# ICEBoard_working.net
KiCad netlist of a schematic drawn in Altium Designer
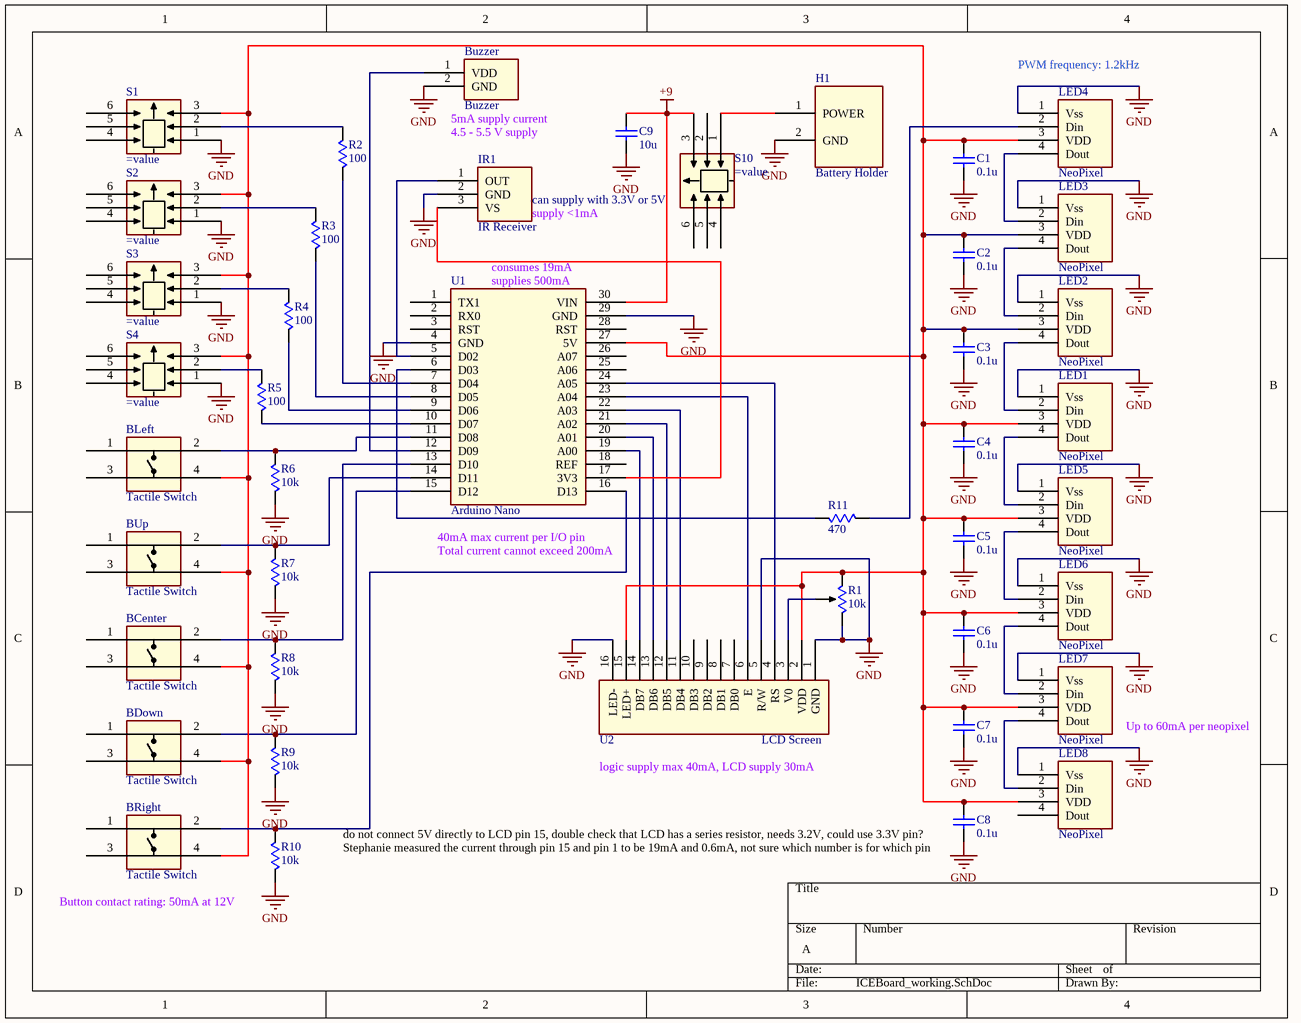
[diagram p0: ICEBoard_working.SchDoc]

(export (version "E")
  (design (tool "Eeschema 10.0.6"))
  (components
    (comp (ref "BCenter")
      (value "Tactile Switch")
      (footprint "PTS645")
      (libsource (lib "PTS645") (part "PTS645"))
    )
    (comp (ref "BDown")
      (value "Tactile Switch")
      (footprint "PTS645")
      (libsource (lib "PTS645") (part "PTS645"))
    )
    (comp (ref "BLeft")
      (value "Tactile Switch")
      (footprint "PTS645")
      (libsource (lib "PTS645") (part "PTS645"))
    )
    (comp (ref "BRight")
      (value "Tactile Switch")
      (footprint "PTS645")
      (libsource (lib "PTS645") (part "PTS645"))
    )
    (comp (ref "BUp")
      (value "Tactile Switch")
      (footprint "PTS645")
      (libsource (lib "PTS645") (part "PTS645"))
    )
    (comp (ref "Buzzer")
      (value "Buzzer")
      (footprint "TP124005")
      (libsource (lib "TP124005") (part "TP124005"))
    )
    (comp (ref "C1") (value "0.1u") (footprint "Capacitor") (libsource (lib "Capacitor") (part "Capacitor")))
    (comp (ref "C2") (value "0.1u") (footprint "Capacitor") (libsource (lib "Capacitor") (part "Capacitor")))
    (comp (ref "C3") (value "0.1u") (footprint "Capacitor") (libsource (lib "Capacitor") (part "Capacitor")))
    (comp (ref "C4") (value "0.1u") (footprint "Capacitor") (libsource (lib "Capacitor") (part "Capacitor")))
    (comp (ref "C5") (value "0.1u") (footprint "Capacitor") (libsource (lib "Capacitor") (part "Capacitor")))
    (comp (ref "C6") (value "0.1u") (footprint "Capacitor") (libsource (lib "Capacitor") (part "Capacitor")))
    (comp (ref "C7") (value "0.1u") (footprint "Capacitor") (libsource (lib "Capacitor") (part "Capacitor")))
    (comp (ref "C8") (value "0.1u") (footprint "Capacitor") (libsource (lib "Capacitor") (part "Capacitor")))
    (comp (ref "C9")
      (value "10u")
      (footprint "PCBComponent_1")
      (libsource (lib "Capacitor") (part "Capacitor"))
    )
    (comp (ref "H1") (value "Battery Holder") (footprint "BH9VPC") (libsource (lib "BH9VPC") (part "BH9VPC")))
    (comp (ref "IR1")
      (value "IR Receiver")
      (footprint "TSOP382")
      (libsource (lib "TSOP382") (part "TSOP382"))
    )
    (comp (ref "LED1")
      (value "NeoPixel")
      (footprint "NeoPixel")
      (libsource (lib "NeoPixel") (part "NeoPixel"))
    )
    (comp (ref "LED2")
      (value "NeoPixel")
      (footprint "NeoPixel")
      (libsource (lib "NeoPixel") (part "NeoPixel"))
    )
    (comp (ref "LED3")
      (value "NeoPixel")
      (footprint "NeoPixel")
      (libsource (lib "NeoPixel") (part "NeoPixel"))
    )
    (comp (ref "LED4")
      (value "NeoPixel")
      (footprint "NeoPixel")
      (libsource (lib "NeoPixel") (part "NeoPixel"))
    )
    (comp (ref "LED5")
      (value "NeoPixel")
      (footprint "NeoPixel")
      (libsource (lib "NeoPixel") (part "NeoPixel"))
    )
    (comp (ref "LED6")
      (value "NeoPixel")
      (footprint "NeoPixel")
      (libsource (lib "NeoPixel") (part "NeoPixel"))
    )
    (comp (ref "LED7")
      (value "NeoPixel")
      (footprint "NeoPixel")
      (libsource (lib "NeoPixel") (part "NeoPixel"))
    )
    (comp (ref "LED8")
      (value "NeoPixel")
      (footprint "NeoPixel")
      (libsource (lib "NeoPixel") (part "NeoPixel"))
    )
    (comp (ref "R1")
      (value "10k")
      (footprint "TC33X")
      (libsource (lib "Resistor - Variable") (part "Resistor - Variable"))
    )
    (comp (ref "R2") (value "100") (footprint "Resistor1608") (libsource (lib "Resistor") (part "Resistor")))
    (comp (ref "R3") (value "100") (footprint "Resistor1608") (libsource (lib "Resistor") (part "Resistor")))
    (comp (ref "R4") (value "100") (footprint "Resistor1608") (libsource (lib "Resistor") (part "Resistor")))
    (comp (ref "R5") (value "100") (footprint "Resistor1608") (libsource (lib "Resistor") (part "Resistor")))
    (comp (ref "R6") (value "10k") (footprint "Resistor1608") (libsource (lib "Resistor") (part "Resistor")))
    (comp (ref "R7") (value "10k") (footprint "Resistor1608") (libsource (lib "Resistor") (part "Resistor")))
    (comp (ref "R8") (value "10k") (footprint "Resistor1608") (libsource (lib "Resistor") (part "Resistor")))
    (comp (ref "R9") (value "10k") (footprint "Resistor1608") (libsource (lib "Resistor") (part "Resistor")))
    (comp (ref "R10") (value "10k") (footprint "Resistor1608") (libsource (lib "Resistor") (part "Resistor")))
    (comp (ref "R11") (value "470") (footprint "Resistor1608") (libsource (lib "Resistor") (part "Resistor")))
    (comp (ref "S1") (value "~") (footprint "MHSS1104") (libsource (lib "MHSS1104") (part "MHSS1104")))
    (comp (ref "S2") (value "~") (footprint "MHSS1104") (libsource (lib "MHSS1104") (part "MHSS1104")))
    (comp (ref "S3") (value "~") (footprint "MHSS1104") (libsource (lib "MHSS1104") (part "MHSS1104")))
    (comp (ref "S4") (value "~") (footprint "MHSS1104") (libsource (lib "MHSS1104") (part "MHSS1104")))
    (comp (ref "S10") (value "~") (footprint "MHSS1104") (libsource (lib "") (part "MHSS1104_1")))
    (comp (ref "U1")
      (value "Arduino Nano")
      (footprint "ArduinoNano")
      (libsource (lib "ArduinoNano") (part "ArduinoNano"))
    )
    (comp (ref "U2")
      (value "LCD Screen")
      (footprint "TC1602A-01T")
      (libsource (lib "TC1602A-01T") (part "TC1602A-01T"))
    )
  )
  (nets
    (net (code "1") (name "+9") (class "Default")
      (node (ref "C9") (pin "1") (pinfunction "1_1") (pintype "passive"))
      (node (ref "S10") (pin "3") (pintype "passive"))
      (node (ref "U1") (pin "30") (pinfunction "VIN_30") (pintype "passive"))
    )
    (net (code "2") (name "GND") (class "Default")
      (node (ref "Buzzer") (pin "2") (pinfunction "GND_2") (pintype "passive"))
      (node (ref "C1") (pin "2") (pinfunction "2_2") (pintype "passive"))
      (node (ref "C2") (pin "2") (pinfunction "2_2") (pintype "passive"))
      (node (ref "C3") (pin "2") (pinfunction "2_2") (pintype "passive"))
      (node (ref "C4") (pin "2") (pinfunction "2_2") (pintype "passive"))
      (node (ref "C5") (pin "2") (pinfunction "2_2") (pintype "passive"))
      (node (ref "C6") (pin "2") (pinfunction "2_2") (pintype "passive"))
      (node (ref "C7") (pin "2") (pinfunction "2_2") (pintype "passive"))
      (node (ref "C8") (pin "2") (pinfunction "2_2") (pintype "passive"))
      (node (ref "C9") (pin "2") (pinfunction "2_2") (pintype "passive"))
      (node (ref "H1") (pin "2") (pinfunction "GND_2") (pintype "passive"))
      (node (ref "IR1") (pin "2") (pinfunction "GND_2") (pintype "passive"))
      (node (ref "LED1") (pin "1") (pinfunction "Vss_1") (pintype "passive"))
      (node (ref "LED2") (pin "1") (pinfunction "Vss_1") (pintype "passive"))
      (node (ref "LED3") (pin "1") (pinfunction "Vss_1") (pintype "passive"))
      (node (ref "LED4") (pin "1") (pinfunction "Vss_1") (pintype "passive"))
      (node (ref "LED5") (pin "1") (pinfunction "Vss_1") (pintype "passive"))
      (node (ref "LED6") (pin "1") (pinfunction "Vss_1") (pintype "passive"))
      (node (ref "LED7") (pin "1") (pinfunction "Vss_1") (pintype "passive"))
      (node (ref "LED8") (pin "1") (pinfunction "Vss_1") (pintype "passive"))
      (node (ref "R1") (pin "1") (pinfunction "1_1") (pintype "passive"))
      (node (ref "R10") (pin "1") (pinfunction "1_1") (pintype "passive"))
      (node (ref "R6") (pin "1") (pinfunction "1_1") (pintype "passive"))
      (node (ref "R7") (pin "1") (pinfunction "1_1") (pintype "passive"))
      (node (ref "R8") (pin "1") (pinfunction "1_1") (pintype "passive"))
      (node (ref "R9") (pin "1") (pinfunction "1_1") (pintype "passive"))
      (node (ref "S1") (pin "1") (pintype "passive"))
      (node (ref "S2") (pin "1") (pintype "passive"))
      (node (ref "S3") (pin "1") (pintype "passive"))
      (node (ref "S4") (pin "1") (pintype "passive"))
      (node (ref "U1") (pin "29") (pinfunction "GND_29") (pintype "passive"))
      (node (ref "U1") (pin "4") (pinfunction "GND_4") (pintype "passive"))
      (node (ref "U2") (pin "1") (pinfunction "GND_1") (pintype "passive"))
      (node (ref "U2") (pin "16") (pinfunction "LED-_16") (pintype "passive"))
      (node (ref "U2") (pin "5") (pinfunction "R/W_5") (pintype "passive"))
    )
    (net (code "3") (name "Net-(Buzzer-VDD)") (class "Default")
      (node (ref "Buzzer") (pin "1") (pinfunction "VDD_1") (pintype "passive"))
      (node (ref "U1") (pin "12") (pinfunction "D09_12") (pintype "passive"))
    )
    (net (code "4") (name "Net-(H1-POWER)") (class "Default")
      (node (ref "H1") (pin "1") (pinfunction "POWER_1") (pintype "passive"))
      (node (ref "S10") (pin "1") (pintype "passive"))
    )
    (net (code "5") (name "Net-(IR1-OUT)") (class "Default")
      (node (ref "IR1") (pin "1") (pinfunction "OUT_1") (pintype "passive"))
      (node (ref "U1") (pin "5") (pinfunction "D02_5") (pintype "passive"))
    )
    (net (code "6") (name "Net-(IR1-VS)") (class "Default")
      (node (ref "IR1") (pin "3") (pinfunction "VS_3") (pintype "passive"))
      (node (ref "U1") (pin "17") (pinfunction "3V3_17") (pintype "passive"))
    )
    (net (code "7") (name "Net-(LED1-Din)") (class "Default")
      (node (ref "LED1") (pin "2") (pinfunction "Din_2") (pintype "passive"))
      (node (ref "LED2") (pin "4") (pinfunction "Dout_4") (pintype "passive"))
    )
    (net (code "8") (name "Net-(LED1-Dout)") (class "Default")
      (node (ref "LED1") (pin "4") (pinfunction "Dout_4") (pintype "passive"))
      (node (ref "LED5") (pin "2") (pinfunction "Din_2") (pintype "passive"))
    )
    (net (code "9") (name "Net-(LED1-VDD)") (class "Default")
      (node (ref "BCenter") (pin "4") (pintype "passive"))
      (node (ref "BDown") (pin "4") (pintype "passive"))
      (node (ref "BLeft") (pin "4") (pintype "passive"))
      (node (ref "BRight") (pin "4") (pintype "passive"))
      (node (ref "BUp") (pin "4") (pintype "passive"))
      (node (ref "C1") (pin "1") (pinfunction "1_1") (pintype "passive"))
      (node (ref "C2") (pin "1") (pinfunction "1_1") (pintype "passive"))
      (node (ref "C3") (pin "1") (pinfunction "1_1") (pintype "passive"))
      (node (ref "C4") (pin "1") (pinfunction "1_1") (pintype "passive"))
      (node (ref "C5") (pin "1") (pinfunction "1_1") (pintype "passive"))
      (node (ref "C6") (pin "1") (pinfunction "1_1") (pintype "passive"))
      (node (ref "C7") (pin "1") (pinfunction "1_1") (pintype "passive"))
      (node (ref "C8") (pin "1") (pinfunction "1_1") (pintype "passive"))
      (node (ref "LED1") (pin "3") (pinfunction "VDD_3") (pintype "passive"))
      (node (ref "LED2") (pin "3") (pinfunction "VDD_3") (pintype "passive"))
      (node (ref "LED3") (pin "3") (pinfunction "VDD_3") (pintype "passive"))
      (node (ref "LED4") (pin "3") (pinfunction "VDD_3") (pintype "passive"))
      (node (ref "LED5") (pin "3") (pinfunction "VDD_3") (pintype "passive"))
      (node (ref "LED6") (pin "3") (pinfunction "VDD_3") (pintype "passive"))
      (node (ref "LED7") (pin "3") (pinfunction "VDD_3") (pintype "passive"))
      (node (ref "LED8") (pin "3") (pinfunction "VDD_3") (pintype "passive"))
      (node (ref "R1") (pin "3") (pinfunction "3_3") (pintype "passive"))
      (node (ref "S1") (pin "3") (pintype "passive"))
      (node (ref "S2") (pin "3") (pintype "passive"))
      (node (ref "S3") (pin "3") (pintype "passive"))
      (node (ref "S4") (pin "3") (pintype "passive"))
      (node (ref "U1") (pin "27") (pinfunction "5V_27") (pintype "passive"))
      (node (ref "U2") (pin "15") (pinfunction "LED+_15") (pintype "passive"))
      (node (ref "U2") (pin "2") (pinfunction "VDD_2") (pintype "passive"))
    )
    (net (code "10") (name "Net-(LED2-Din)") (class "Default")
      (node (ref "LED2") (pin "2") (pinfunction "Din_2") (pintype "passive"))
      (node (ref "LED3") (pin "4") (pinfunction "Dout_4") (pintype "passive"))
    )
    (net (code "11") (name "Net-(LED3-Din)") (class "Default")
      (node (ref "LED3") (pin "2") (pinfunction "Din_2") (pintype "passive"))
      (node (ref "LED4") (pin "4") (pinfunction "Dout_4") (pintype "passive"))
    )
    (net (code "12") (name "Net-(LED4-Din)") (class "Default")
      (node (ref "LED4") (pin "2") (pinfunction "Din_2") (pintype "passive"))
      (node (ref "R11") (pin "2") (pinfunction "2_2") (pintype "passive"))
    )
    (net (code "13") (name "Net-(LED5-Dout)") (class "Default")
      (node (ref "LED5") (pin "4") (pinfunction "Dout_4") (pintype "passive"))
      (node (ref "LED6") (pin "2") (pinfunction "Din_2") (pintype "passive"))
    )
    (net (code "14") (name "Net-(LED6-Dout)") (class "Default")
      (node (ref "LED6") (pin "4") (pinfunction "Dout_4") (pintype "passive"))
      (node (ref "LED7") (pin "2") (pinfunction "Din_2") (pintype "passive"))
    )
    (net (code "15") (name "Net-(LED7-Dout)") (class "Default")
      (node (ref "LED7") (pin "4") (pinfunction "Dout_4") (pintype "passive"))
      (node (ref "LED8") (pin "2") (pinfunction "Din_2") (pintype "passive"))
    )
    (net (code "16") (name "Net-(R2-Pad2)") (class "Default")
      (node (ref "R2") (pin "2") (pinfunction "2_2") (pintype "passive"))
      (node (ref "S1") (pin "2") (pintype "passive"))
    )
    (net (code "17") (name "Net-(R3-Pad2)") (class "Default")
      (node (ref "R3") (pin "2") (pinfunction "2_2") (pintype "passive"))
      (node (ref "S2") (pin "2") (pintype "passive"))
    )
    (net (code "18") (name "Net-(R4-Pad2)") (class "Default")
      (node (ref "R4") (pin "2") (pinfunction "2_2") (pintype "passive"))
      (node (ref "S3") (pin "2") (pintype "passive"))
    )
    (net (code "19") (name "Net-(R5-Pad2)") (class "Default")
      (node (ref "R5") (pin "2") (pinfunction "2_2") (pintype "passive"))
      (node (ref "S4") (pin "2") (pintype "passive"))
    )
    (net (code "20") (name "Net-(U1-A00)") (class "Default")
      (node (ref "U1") (pin "19") (pinfunction "A00_19") (pintype "passive"))
      (node (ref "U2") (pin "14") (pinfunction "DB7_14") (pintype "passive"))
    )
    (net (code "21") (name "Net-(U1-A01)") (class "Default")
      (node (ref "U1") (pin "20") (pinfunction "A01_20") (pintype "passive"))
      (node (ref "U2") (pin "13") (pinfunction "DB6_13") (pintype "passive"))
    )
    (net (code "22") (name "Net-(U1-A02)") (class "Default")
      (node (ref "U1") (pin "21") (pinfunction "A02_21") (pintype "passive"))
      (node (ref "U2") (pin "12") (pinfunction "DB5_12") (pintype "passive"))
    )
    (net (code "23") (name "Net-(U1-A03)") (class "Default")
      (node (ref "U1") (pin "22") (pinfunction "A03_22") (pintype "passive"))
      (node (ref "U2") (pin "11") (pinfunction "DB4_11") (pintype "passive"))
    )
    (net (code "24") (name "Net-(U1-A04)") (class "Default")
      (node (ref "U1") (pin "23") (pinfunction "A04_23") (pintype "passive"))
      (node (ref "U2") (pin "6") (pinfunction "E_6") (pintype "passive"))
    )
    (net (code "25") (name "Net-(U1-A05)") (class "Default")
      (node (ref "U1") (pin "24") (pinfunction "A05_24") (pintype "passive"))
      (node (ref "U2") (pin "4") (pinfunction "RS_4") (pintype "passive"))
    )
    (net (code "26") (name "Net-(U1-D03)") (class "Default")
      (node (ref "R11") (pin "1") (pinfunction "1_1") (pintype "passive"))
      (node (ref "U1") (pin "6") (pinfunction "D03_6") (pintype "passive"))
    )
    (net (code "27") (name "Net-(U1-D04)") (class "Default")
      (node (ref "R2") (pin "1") (pinfunction "1_1") (pintype "passive"))
      (node (ref "U1") (pin "7") (pinfunction "D04_7") (pintype "passive"))
    )
    (net (code "28") (name "Net-(U1-D05)") (class "Default")
      (node (ref "R3") (pin "1") (pinfunction "1_1") (pintype "passive"))
      (node (ref "U1") (pin "8") (pinfunction "D05_8") (pintype "passive"))
    )
    (net (code "29") (name "Net-(U1-D06)") (class "Default")
      (node (ref "R4") (pin "1") (pinfunction "1_1") (pintype "passive"))
      (node (ref "U1") (pin "9") (pinfunction "D06_9") (pintype "passive"))
    )
    (net (code "30") (name "Net-(U1-D07)") (class "Default")
      (node (ref "R5") (pin "1") (pinfunction "1_1") (pintype "passive"))
      (node (ref "U1") (pin "10") (pinfunction "D07_10") (pintype "passive"))
    )
    (net (code "31") (name "Net-(U1-D08)") (class "Default")
      (node (ref "BLeft") (pin "2") (pintype "passive"))
      (node (ref "R6") (pin "2") (pinfunction "2_2") (pintype "passive"))
      (node (ref "U1") (pin "11") (pinfunction "D08_11") (pintype "passive"))
    )
    (net (code "32") (name "Net-(U1-D10)") (class "Default")
      (node (ref "BCenter") (pin "2") (pintype "passive"))
      (node (ref "R8") (pin "2") (pinfunction "2_2") (pintype "passive"))
      (node (ref "U1") (pin "13") (pinfunction "D10_13") (pintype "passive"))
    )
    (net (code "33") (name "Net-(U1-D11)") (class "Default")
      (node (ref "BUp") (pin "2") (pintype "passive"))
      (node (ref "R7") (pin "2") (pinfunction "2_2") (pintype "passive"))
      (node (ref "U1") (pin "14") (pinfunction "D11_14") (pintype "passive"))
    )
    (net (code "34") (name "Net-(U1-D12)") (class "Default")
      (node (ref "BDown") (pin "2") (pintype "passive"))
      (node (ref "R9") (pin "2") (pinfunction "2_2") (pintype "passive"))
      (node (ref "U1") (pin "15") (pinfunction "D12_15") (pintype "passive"))
    )
    (net (code "35") (name "Net-(U1-D13)") (class "Default")
      (node (ref "BRight") (pin "2") (pintype "passive"))
      (node (ref "R10") (pin "2") (pinfunction "2_2") (pintype "passive"))
      (node (ref "U1") (pin "16") (pinfunction "D13_16") (pintype "passive"))
    )
    (net (code "36") (name "Net-(U2-V0)") (class "Default")
      (node (ref "R1") (pin "2") (pinfunction "2_2") (pintype "passive"))
      (node (ref "U2") (pin "3") (pinfunction "V0_3") (pintype "passive"))
    )
    (net (code "37") (name "unconnected-(BCenter-Pad1)") (class "Default")
      (node (ref "BCenter") (pin "1") (pintype "passive"))
    )
    (net (code "38") (name "unconnected-(BCenter-Pad3)") (class "Default")
      (node (ref "BCenter") (pin "3") (pintype "passive"))
    )
    (net (code "39") (name "unconnected-(BDown-Pad1)") (class "Default")
      (node (ref "BDown") (pin "1") (pintype "passive"))
    )
    (net (code "40") (name "unconnected-(BDown-Pad3)") (class "Default")
      (node (ref "BDown") (pin "3") (pintype "passive"))
    )
    (net (code "41") (name "unconnected-(BLeft-Pad1)") (class "Default")
      (node (ref "BLeft") (pin "1") (pintype "passive"))
    )
    (net (code "42") (name "unconnected-(BLeft-Pad3)") (class "Default")
      (node (ref "BLeft") (pin "3") (pintype "passive"))
    )
    (net (code "43") (name "unconnected-(BRight-Pad1)") (class "Default")
      (node (ref "BRight") (pin "1") (pintype "passive"))
    )
    (net (code "44") (name "unconnected-(BRight-Pad3)") (class "Default")
      (node (ref "BRight") (pin "3") (pintype "passive"))
    )
    (net (code "45") (name "unconnected-(BUp-Pad1)") (class "Default")
      (node (ref "BUp") (pin "1") (pintype "passive"))
    )
    (net (code "46") (name "unconnected-(BUp-Pad3)") (class "Default")
      (node (ref "BUp") (pin "3") (pintype "passive"))
    )
    (net (code "47") (name "unconnected-(LED8-Dout-Pad4)") (class "Default")
      (node (ref "LED8") (pin "4") (pinfunction "Dout_4") (pintype "passive"))
    )
    (net (code "48") (name "unconnected-(S1-Pad4)") (class "Default")
      (node (ref "S1") (pin "4") (pintype "passive"))
    )
    (net (code "49") (name "unconnected-(S1-Pad5)") (class "Default")
      (node (ref "S1") (pin "5") (pintype "passive"))
    )
    (net (code "50") (name "unconnected-(S1-Pad6)") (class "Default")
      (node (ref "S1") (pin "6") (pintype "passive"))
    )
    (net (code "51") (name "unconnected-(S2-Pad4)") (class "Default")
      (node (ref "S2") (pin "4") (pintype "passive"))
    )
    (net (code "52") (name "unconnected-(S2-Pad5)") (class "Default")
      (node (ref "S2") (pin "5") (pintype "passive"))
    )
    (net (code "53") (name "unconnected-(S2-Pad6)") (class "Default")
      (node (ref "S2") (pin "6") (pintype "passive"))
    )
    (net (code "54") (name "unconnected-(S3-Pad4)") (class "Default")
      (node (ref "S3") (pin "4") (pintype "passive"))
    )
    (net (code "55") (name "unconnected-(S3-Pad5)") (class "Default")
      (node (ref "S3") (pin "5") (pintype "passive"))
    )
    (net (code "56") (name "unconnected-(S3-Pad6)") (class "Default")
      (node (ref "S3") (pin "6") (pintype "passive"))
    )
    (net (code "57") (name "unconnected-(S4-Pad4)") (class "Default")
      (node (ref "S4") (pin "4") (pintype "passive"))
    )
    (net (code "58") (name "unconnected-(S4-Pad5)") (class "Default")
      (node (ref "S4") (pin "5") (pintype "passive"))
    )
    (net (code "59") (name "unconnected-(S4-Pad6)") (class "Default")
      (node (ref "S4") (pin "6") (pintype "passive"))
    )
    (net (code "60") (name "unconnected-(S10-Pad2)") (class "Default")
      (node (ref "S10") (pin "2") (pintype "passive"))
    )
    (net (code "61") (name "unconnected-(S10-Pad4)") (class "Default")
      (node (ref "S10") (pin "4") (pintype "passive"))
    )
    (net (code "62") (name "unconnected-(S10-Pad5)") (class "Default")
      (node (ref "S10") (pin "5") (pintype "passive"))
    )
    (net (code "63") (name "unconnected-(S10-Pad6)") (class "Default")
      (node (ref "S10") (pin "6") (pintype "passive"))
    )
    (net (code "64") (name "unconnected-(U1-A06-Pad25)") (class "Default")
      (node (ref "U1") (pin "25") (pinfunction "A06_25") (pintype "passive"))
    )
    (net (code "65") (name "unconnected-(U1-A07-Pad26)") (class "Default")
      (node (ref "U1") (pin "26") (pinfunction "A07_26") (pintype "passive"))
    )
    (net (code "66") (name "unconnected-(U1-REF-Pad18)") (class "Default")
      (node (ref "U1") (pin "18") (pinfunction "REF_18") (pintype "passive"))
    )
    (net (code "67") (name "unconnected-(U1-RST-Pad3)") (class "Default")
      (node (ref "U1") (pin "3") (pinfunction "RST_3") (pintype "passive"))
    )
    (net (code "68") (name "unconnected-(U1-RST-Pad28)") (class "Default")
      (node (ref "U1") (pin "28") (pinfunction "RST_28") (pintype "passive"))
    )
    (net (code "69") (name "unconnected-(U1-RX0-Pad2)") (class "Default")
      (node (ref "U1") (pin "2") (pinfunction "RX0_2") (pintype "passive"))
    )
    (net (code "70") (name "unconnected-(U1-TX1-Pad1)") (class "Default")
      (node (ref "U1") (pin "1") (pinfunction "TX1_1") (pintype "passive"))
    )
    (net (code "71") (name "unconnected-(U2-DB0-Pad7)") (class "Default")
      (node (ref "U2") (pin "7") (pinfunction "DB0_7") (pintype "passive"))
    )
    (net (code "72") (name "unconnected-(U2-DB1-Pad8)") (class "Default")
      (node (ref "U2") (pin "8") (pinfunction "DB1_8") (pintype "passive"))
    )
    (net (code "73") (name "unconnected-(U2-DB2-Pad9)") (class "Default")
      (node (ref "U2") (pin "9") (pinfunction "DB2_9") (pintype "passive"))
    )
    (net (code "74") (name "unconnected-(U2-DB3-Pad10)") (class "Default")
      (node (ref "U2") (pin "10") (pinfunction "DB3_10") (pintype "passive"))
    )
  )
)
